# LM741.net
KiCad netlist of a schematic drawn in Altium Designer
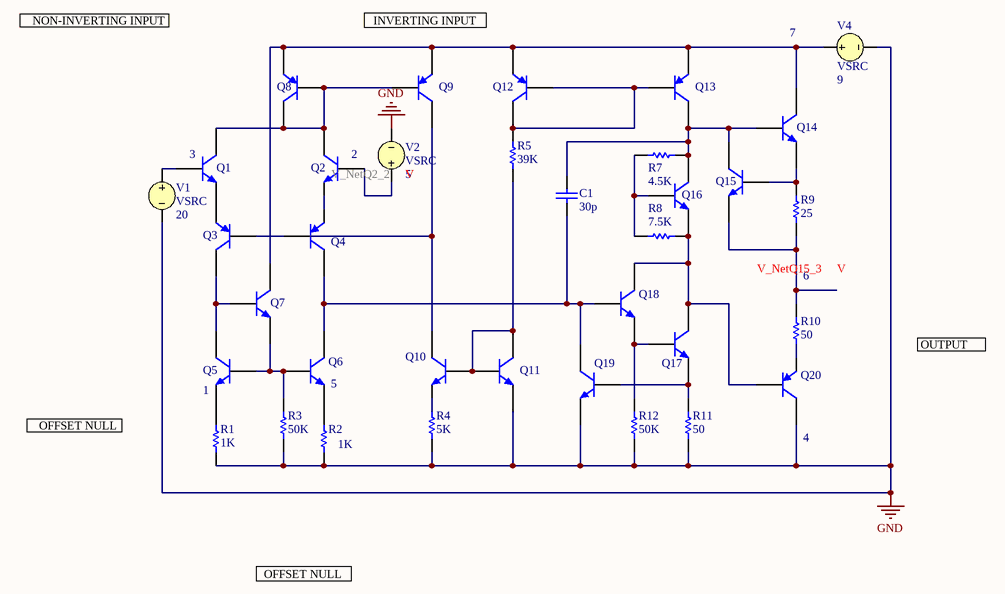
[diagram p0: ОУ LM741.SchDoc]

(export (version "E")
  (design (tool "Eeschema 10.0.6"))
  (components
    (comp (ref "C1")
      (value "30p")
      (description "Capacitor")
      (libsource (lib "Simulation Generic Components") (part "Capacitor"))
    )
    (comp (ref "Q1")
      (value "Bipolar  NPN 3 Pins  Transistor VBIC Model")
      (libsource (lib "Simulation Generic Components") (part "BJT NPN VBIC"))
    )
    (comp (ref "Q2")
      (value "Bipolar  NPN 3 Pins  Transistor VBIC Model")
      (libsource (lib "Simulation Generic Components") (part "BJT NPN VBIC"))
    )
    (comp (ref "Q3")
      (value "Bipolar  PNP 3 Pins  Transistor  Gummel-Poon Model")
      (libsource (lib "Simulation Generic Components") (part "BJT PNP GP"))
    )
    (comp (ref "Q4")
      (value "Bipolar  PNP 3 Pins  Transistor  Gummel-Poon Model")
      (libsource (lib "Simulation Generic Components") (part "BJT PNP GP"))
    )
    (comp (ref "Q5")
      (value "Bipolar  NPN 3 Pins  Transistor VBIC Model")
      (libsource (lib "Simulation Generic Components") (part "BJT NPN VBIC"))
    )
    (comp (ref "Q6")
      (value "Bipolar  NPN 3 Pins  Transistor VBIC Model")
      (libsource (lib "Simulation Generic Components") (part "BJT NPN VBIC"))
    )
    (comp (ref "Q7")
      (value "Bipolar  NPN 3 Pins  Transistor VBIC Model")
      (libsource (lib "Simulation Generic Components") (part "BJT NPN VBIC"))
    )
    (comp (ref "Q8")
      (value "Bipolar  PNP 3 Pins  Transistor  Gummel-Poon Model")
      (libsource (lib "Simulation Generic Components") (part "BJT PNP GP"))
    )
    (comp (ref "Q9")
      (value "Bipolar  PNP 3 Pins  Transistor  Gummel-Poon Model")
      (libsource (lib "Simulation Generic Components") (part "BJT PNP GP"))
    )
    (comp (ref "Q10")
      (value "Bipolar  NPN 3 Pins  Transistor VBIC Model")
      (libsource (lib "Simulation Generic Components") (part "BJT NPN VBIC"))
    )
    (comp (ref "Q11")
      (value "Bipolar  NPN 3 Pins  Transistor VBIC Model")
      (libsource (lib "Simulation Generic Components") (part "BJT NPN VBIC"))
    )
    (comp (ref "Q12")
      (value "Bipolar  PNP 3 Pins  Transistor  Gummel-Poon Model")
      (libsource (lib "Simulation Generic Components") (part "BJT PNP GP"))
    )
    (comp (ref "Q13")
      (value "Bipolar  PNP 3 Pins  Transistor  Gummel-Poon Model")
      (libsource (lib "Simulation Generic Components") (part "BJT PNP GP"))
    )
    (comp (ref "Q14")
      (value "Bipolar  NPN 3 Pins  Transistor VBIC Model")
      (libsource (lib "Simulation Generic Components") (part "BJT NPN VBIC"))
    )
    (comp (ref "Q15")
      (value "Bipolar  NPN 3 Pins  Transistor VBIC Model")
      (libsource (lib "Simulation Generic Components") (part "BJT NPN VBIC"))
    )
    (comp (ref "Q16")
      (value "Bipolar  NPN 3 Pins  Transistor VBIC Model")
      (libsource (lib "Simulation Generic Components") (part "BJT NPN VBIC"))
    )
    (comp (ref "Q17")
      (value "Bipolar  NPN 3 Pins  Transistor VBIC Model")
      (libsource (lib "Simulation Generic Components") (part "BJT NPN VBIC"))
    )
    (comp (ref "Q18")
      (value "Bipolar  NPN 3 Pins  Transistor VBIC Model")
      (libsource (lib "Simulation Generic Components") (part "BJT NPN VBIC"))
    )
    (comp (ref "Q19")
      (value "Bipolar  NPN 3 Pins  Transistor VBIC Model")
      (libsource (lib "Simulation Generic Components") (part "BJT NPN VBIC"))
    )
    (comp (ref "Q20")
      (value "Bipolar  PNP 3 Pins   Transistor  VBIC Model")
      (libsource (lib "Simulation Generic Components") (part "BJT PNP VBIC"))
    )
    (comp (ref "R1")
      (value "1K")
      (description "Resistor")
      (libsource (lib "Simulation Generic Components") (part "Resistor"))
    )
    (comp (ref "R2")
      (value "1K")
      (description "Resistor")
      (libsource (lib "Simulation Generic Components") (part "Resistor"))
    )
    (comp (ref "R3")
      (value "50K")
      (description "Resistor")
      (libsource (lib "Simulation Generic Components") (part "Resistor"))
    )
    (comp (ref "R4")
      (value "5K")
      (description "Resistor")
      (libsource (lib "Simulation Generic Components") (part "Resistor"))
    )
    (comp (ref "R5")
      (value "39K")
      (description "Resistor")
      (libsource (lib "Simulation Generic Components") (part "Resistor"))
    )
    (comp (ref "R7")
      (value "4.5K")
      (description "Resistor")
      (libsource (lib "Simulation Generic Components") (part "Resistor"))
    )
    (comp (ref "R8")
      (value "7.5K")
      (description "Resistor")
      (libsource (lib "Simulation Generic Components") (part "Resistor"))
    )
    (comp (ref "R9")
      (value "25")
      (description "Resistor")
      (libsource (lib "Simulation Generic Components") (part "Resistor"))
    )
    (comp (ref "R10")
      (value "50")
      (description "Resistor")
      (libsource (lib "Simulation Generic Components") (part "Resistor"))
    )
    (comp (ref "R11")
      (value "50")
      (description "Resistor")
      (libsource (lib "Simulation Generic Components") (part "Resistor"))
    )
    (comp (ref "R12")
      (value "50K")
      (description "Resistor")
      (libsource (lib "Simulation Generic Components") (part "Resistor"))
    )
    (comp (ref "V1")
      (value "VSRC")
      (description "Voltage Source")
      (fields (field (name "ALTIUM_VALUE") "20") (field (name "PUBLISHER") "Altium Limited"))
      (libsource (lib "Simulation Generic Components") (part "VSRC"))
    )
    (comp (ref "V2")
      (value "VSRC")
      (description "Voltage Source")
      (fields (field (name "DC MAGNITUDE") "5") (field (name "PUBLISHER") "Altium Limited"))
      (libsource (lib "Simulation Generic Components") (part "VSRC"))
    )
    (comp (ref "V4")
      (value "VSRC")
      (description "Voltage Source")
      (fields (field (name "ALTIUM_VALUE") "9") (field (name "PUBLISHER") "Altium Limited"))
      (libsource (lib "Simulation Generic Components") (part "VSRC"))
    )
  )
  (nets
    (net (code "5") (name "GND") (class "Default")
      (node (ref "Q11") (pin "3") (pinfunction "E_3") (pintype "passive"))
      (node (ref "Q19") (pin "3") (pinfunction "E_3") (pintype "passive"))
      (node (ref "Q20") (pin "1") (pinfunction "C_1") (pintype "passive"))
      (node (ref "R1") (pin "1") (pinfunction "1_1") (pintype "passive"))
      (node (ref "R11") (pin "1") (pinfunction "1_1") (pintype "passive"))
      (node (ref "R12") (pin "1") (pinfunction "1_1") (pintype "passive"))
      (node (ref "R2") (pin "1") (pinfunction "1_1") (pintype "passive"))
      (node (ref "R3") (pin "1") (pinfunction "1_1") (pintype "passive"))
      (node (ref "R4") (pin "1") (pinfunction "1_1") (pintype "passive"))
      (node (ref "V1") (pin "2") (pinfunction "2_2") (pintype "passive"))
      (node (ref "V2") (pin "2") (pinfunction "2_2") (pintype "passive"))
      (node (ref "V4") (pin "2") (pinfunction "2_2") (pintype "passive"))
    )
    (net (code "6") (name "Net-(Q1-B)") (class "Default")
      (node (ref "Q1") (pin "2") (pinfunction "B_2") (pintype "passive"))
      (node (ref "V1") (pin "1") (pinfunction "1_1") (pintype "passive"))
    )
    (net (code "7") (name "Net-(Q1-C)") (class "Default")
      (node (ref "Q1") (pin "1") (pinfunction "C_1") (pintype "passive"))
      (node (ref "Q2") (pin "1") (pinfunction "C_1") (pintype "passive"))
      (node (ref "Q8") (pin "1") (pinfunction "C_1") (pintype "passive"))
      (node (ref "Q8") (pin "2") (pinfunction "B_2") (pintype "passive"))
      (node (ref "Q9") (pin "2") (pinfunction "B_2") (pintype "passive"))
    )
    (net (code "8") (name "Net-(Q2-B)") (class "Default")
      (node (ref "Q2") (pin "2") (pinfunction "B_2") (pintype "passive"))
      (node (ref "V2") (pin "1") (pinfunction "1_1") (pintype "passive"))
    )
    (net (code "9") (name "Net-(Q2-E)") (class "Default")
      (node (ref "Q2") (pin "3") (pinfunction "E_3") (pintype "passive"))
      (node (ref "Q4") (pin "3") (pinfunction "E_3") (pintype "passive"))
    )
    (net (code "10") (name "Net-(Q3-B)") (class "Default")
      (node (ref "Q3") (pin "2") (pinfunction "B_2") (pintype "passive"))
      (node (ref "Q4") (pin "2") (pinfunction "B_2") (pintype "passive"))
    )
    (net (code "11") (name "Net-(Q3-C)") (class "Default")
      (node (ref "Q3") (pin "1") (pinfunction "C_1") (pintype "passive"))
      (node (ref "Q5") (pin "1") (pinfunction "C_1") (pintype "passive"))
      (node (ref "Q7") (pin "2") (pinfunction "B_2") (pintype "passive"))
    )
    (net (code "12") (name "Net-(Q5-B)") (class "Default")
      (node (ref "Q5") (pin "2") (pinfunction "B_2") (pintype "passive"))
      (node (ref "Q6") (pin "2") (pinfunction "B_2") (pintype "passive"))
      (node (ref "Q7") (pin "3") (pinfunction "E_3") (pintype "passive"))
      (node (ref "R3") (pin "2") (pinfunction "2_2") (pintype "passive"))
    )
    (net (code "13") (name "Net-(Q5-E)") (class "Default")
      (node (ref "Q5") (pin "3") (pinfunction "E_3") (pintype "passive"))
      (node (ref "R1") (pin "2") (pinfunction "2_2") (pintype "passive"))
    )
    (net (code "14") (name "Net-(Q6-E)") (class "Default")
      (node (ref "Q6") (pin "3") (pinfunction "E_3") (pintype "passive"))
      (node (ref "R2") (pin "2") (pinfunction "2_2") (pintype "passive"))
    )
    (net (code "15") (name "Net-(Q10-B)") (class "Default")
      (node (ref "Q10") (pin "2") (pinfunction "B_2") (pintype "passive"))
      (node (ref "Q11") (pin "1") (pinfunction "C_1") (pintype "passive"))
      (node (ref "Q11") (pin "2") (pinfunction "B_2") (pintype "passive"))
      (node (ref "R5") (pin "1") (pinfunction "1_1") (pintype "passive"))
    )
    (net (code "16") (name "Net-(Q10-C)") (class "Default")
      (node (ref "Q10") (pin "1") (pinfunction "C_1") (pintype "passive"))
      (node (ref "Q9") (pin "1") (pinfunction "C_1") (pintype "passive"))
    )
    (net (code "17") (name "Net-(Q10-E)") (class "Default")
      (node (ref "Q10") (pin "3") (pinfunction "E_3") (pintype "passive"))
      (node (ref "R4") (pin "2") (pinfunction "2_2") (pintype "passive"))
    )
    (net (code "18") (name "Net-(Q12-B)") (class "Default")
      (node (ref "Q12") (pin "1") (pinfunction "C_1") (pintype "passive"))
      (node (ref "Q12") (pin "2") (pinfunction "B_2") (pintype "passive"))
      (node (ref "Q13") (pin "2") (pinfunction "B_2") (pintype "passive"))
      (node (ref "R5") (pin "2") (pinfunction "2_2") (pintype "passive"))
    )
    (net (code "19") (name "Net-(Q12-E)") (class "Default")
      (node (ref "Q12") (pin "3") (pinfunction "E_3") (pintype "passive"))
      (node (ref "Q13") (pin "3") (pinfunction "E_3") (pintype "passive"))
      (node (ref "Q14") (pin "1") (pinfunction "C_1") (pintype "passive"))
      (node (ref "Q7") (pin "1") (pinfunction "C_1") (pintype "passive"))
      (node (ref "Q8") (pin "3") (pinfunction "E_3") (pintype "passive"))
      (node (ref "Q9") (pin "3") (pinfunction "E_3") (pintype "passive"))
      (node (ref "V4") (pin "1") (pinfunction "1_1") (pintype "passive"))
    )
    (net (code "20") (name "Net-(Q13-C)") (class "Default")
      (node (ref "C1") (pin "2") (pinfunction "2_2") (pintype "passive"))
      (node (ref "Q13") (pin "1") (pinfunction "C_1") (pintype "passive"))
      (node (ref "Q14") (pin "2") (pinfunction "B_2") (pintype "passive"))
      (node (ref "Q15") (pin "1") (pinfunction "C_1") (pintype "passive"))
      (node (ref "Q16") (pin "1") (pinfunction "C_1") (pintype "passive"))
      (node (ref "R7") (pin "1") (pinfunction "1_1") (pintype "passive"))
    )
    (net (code "21") (name "Net-(Q14-E)") (class "Default")
      (node (ref "Q14") (pin "3") (pinfunction "E_3") (pintype "passive"))
      (node (ref "Q15") (pin "2") (pinfunction "B_2") (pintype "passive"))
      (node (ref "R9") (pin "2") (pinfunction "2_2") (pintype "passive"))
    )
    (net (code "22") (name "Net-(Q15-E)") (class "Default")
      (node (ref "Q15") (pin "3") (pinfunction "E_3") (pintype "passive"))
      (node (ref "R10") (pin "2") (pinfunction "2_2") (pintype "passive"))
      (node (ref "R9") (pin "1") (pinfunction "1_1") (pintype "passive"))
    )
    (net (code "23") (name "Net-(Q16-B)") (class "Default")
      (node (ref "Q16") (pin "2") (pinfunction "B_2") (pintype "passive"))
      (node (ref "R7") (pin "2") (pinfunction "2_2") (pintype "passive"))
      (node (ref "R8") (pin "2") (pinfunction "2_2") (pintype "passive"))
    )
    (net (code "24") (name "Net-(Q16-E)") (class "Default")
      (node (ref "Q16") (pin "3") (pinfunction "E_3") (pintype "passive"))
      (node (ref "Q17") (pin "1") (pinfunction "C_1") (pintype "passive"))
      (node (ref "Q18") (pin "1") (pinfunction "C_1") (pintype "passive"))
      (node (ref "Q20") (pin "2") (pinfunction "B_2") (pintype "passive"))
      (node (ref "R8") (pin "1") (pinfunction "1_1") (pintype "passive"))
    )
    (net (code "25") (name "Net-(Q17-B)") (class "Default")
      (node (ref "Q17") (pin "2") (pinfunction "B_2") (pintype "passive"))
      (node (ref "Q18") (pin "3") (pinfunction "E_3") (pintype "passive"))
      (node (ref "R12") (pin "2") (pinfunction "2_2") (pintype "passive"))
    )
    (net (code "26") (name "Net-(Q17-E)") (class "Default")
      (node (ref "Q17") (pin "3") (pinfunction "E_3") (pintype "passive"))
      (node (ref "Q19") (pin "2") (pinfunction "B_2") (pintype "passive"))
      (node (ref "R11") (pin "2") (pinfunction "2_2") (pintype "passive"))
    )
    (net (code "27") (name "Net-(Q18-B)") (class "Default")
      (node (ref "C1") (pin "1") (pinfunction "1_1") (pintype "passive"))
      (node (ref "Q18") (pin "2") (pinfunction "B_2") (pintype "passive"))
      (node (ref "Q19") (pin "1") (pinfunction "C_1") (pintype "passive"))
      (node (ref "Q4") (pin "1") (pinfunction "C_1") (pintype "passive"))
      (node (ref "Q6") (pin "1") (pinfunction "C_1") (pintype "passive"))
    )
    (net (code "28") (name "Net-(Q20-E)") (class "Default")
      (node (ref "Q20") (pin "3") (pinfunction "E_3") (pintype "passive"))
      (node (ref "R10") (pin "1") (pinfunction "1_1") (pintype "passive"))
    )
    (net (code "29") (name "unconnected-(Q1-E-Pad3)") (class "Default")
      (node (ref "Q1") (pin "3") (pinfunction "E_3") (pintype "passive"))
    )
    (net (code "30") (name "unconnected-(Q3-E-Pad3)") (class "Default")
      (node (ref "Q3") (pin "3") (pinfunction "E_3") (pintype "passive"))
    )
  )
)
